# intput-selector.net
KiCad netlist of a schematic drawn in EAGLE
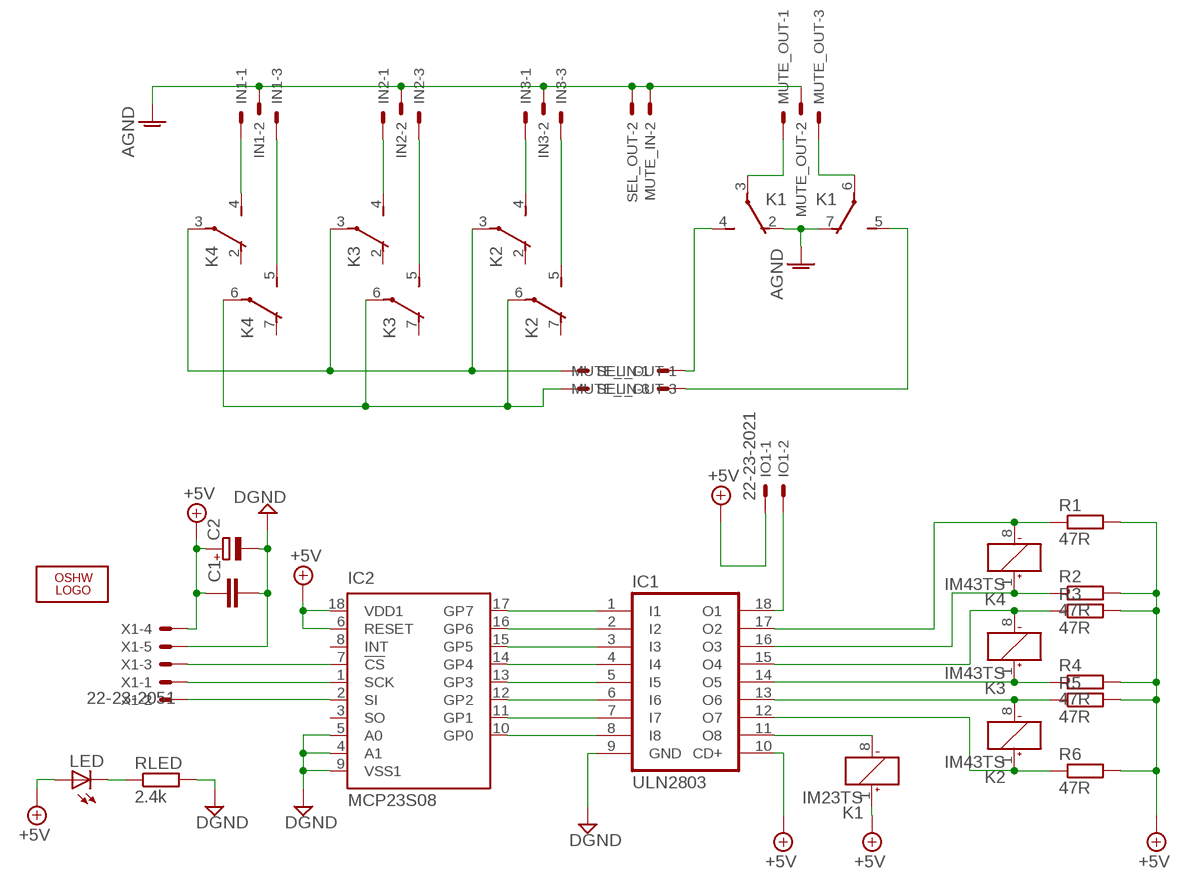
[diagram p0: schematic, sheet 1]

(export (version "E")
  (design (tool "Eeschema 10.0.6"))
  (components
    (comp (ref "C1")
      (value "C-EUC1206")
      (footprint "eagle-import:C1206")
      (libsource (lib "eagle-import") (part "C-EUC1206"))
    )
    (comp (ref "C2")
      (value "CPOL-EUC")
      (footprint "eagle-import:PANASONIC_C")
      (libsource (lib "eagle-import") (part "CPOL-EUC"))
    )
    (comp (ref "IC1")
      (value "ULN2803")
      (footprint "eagle-import:SO-18W")
      (libsource (lib "eagle-import") (part "ULN2803ADW"))
    )
    (comp (ref "IC2")
      (value "MCP23S08")
      (footprint "eagle-import:SO-18W")
      (libsource (lib "eagle-import") (part "MCP23S08-E/SO"))
    )
    (comp (ref "IN1")
      (value "22-23-2031")
      (footprint "eagle-import:22-23-2031")
      (fields (field (name "MF") "MOLEX"))
      (libsource (lib "eagle-import") (part "22-23-2031"))
    )
    (comp (ref "IN2")
      (value "22-23-2031")
      (footprint "eagle-import:22-23-2031")
      (fields (field (name "MF") "MOLEX"))
      (libsource (lib "eagle-import") (part "22-23-2031"))
    )
    (comp (ref "IN3")
      (value "22-23-2031")
      (footprint "eagle-import:22-23-2031")
      (fields (field (name "MF") "MOLEX"))
      (libsource (lib "eagle-import") (part "22-23-2031"))
    )
    (comp (ref "IO1")
      (value "22-23-2021")
      (footprint "eagle-import:22-23-2021")
      (fields (field (name "MF") "MOLEX"))
      (libsource (lib "eagle-import") (part "22-23-2021"))
    )
    (comp (ref "K1")
      (value "IM23TS")
      (footprint "eagle-import:IM43TS")
      (libsource (lib "eagle-import") (part "IM23TS"))
    )
    (comp (ref "K2")
      (value "IM43TS")
      (footprint "eagle-import:IM43TS")
      (libsource (lib "eagle-import") (part "IM43TS"))
    )
    (comp (ref "K3")
      (value "IM43TS")
      (footprint "eagle-import:IM43TS")
      (libsource (lib "eagle-import") (part "IM43TS"))
    )
    (comp (ref "K4")
      (value "IM43TS")
      (footprint "eagle-import:IM43TS")
      (libsource (lib "eagle-import") (part "IM43TS"))
    )
    (comp (ref "LED")
      (value "LEDCHIPLED_1206")
      (footprint "eagle-import:CHIPLED_1206")
      (libsource (lib "eagle-import") (part "LEDCHIPLED_1206"))
    )
    (comp (ref "LOGO1")
      (value "OSHW_LOGO_FILLX0200-NT")
      (footprint "eagle-import:OSHW_FILLX200_NOTEXT")
      (libsource (lib "eagle-import") (part "OSHW_LOGO_FILLX0200-NT"))
    )
    (comp (ref "MUTE_IN")
      (value "22-23-2031")
      (footprint "eagle-import:22-23-2031")
      (fields (field (name "MF") "MOLEX"))
      (libsource (lib "eagle-import") (part "22-23-2031"))
    )
    (comp (ref "MUTE_OUT")
      (value "22-23-2031")
      (footprint "eagle-import:22-23-2031")
      (fields (field (name "MF") "MOLEX"))
      (libsource (lib "eagle-import") (part "22-23-2031"))
    )
    (comp (ref "R1")
      (value "47R")
      (footprint "eagle-import:R1206")
      (libsource (lib "eagle-import") (part "R-EU_R1206"))
    )
    (comp (ref "R2")
      (value "47R")
      (footprint "eagle-import:R1206")
      (libsource (lib "eagle-import") (part "R-EU_R1206"))
    )
    (comp (ref "R3")
      (value "47R")
      (footprint "eagle-import:R1206")
      (libsource (lib "eagle-import") (part "R-EU_R1206"))
    )
    (comp (ref "R4")
      (value "47R")
      (footprint "eagle-import:R1206")
      (libsource (lib "eagle-import") (part "R-EU_R1206"))
    )
    (comp (ref "R5")
      (value "47R")
      (footprint "eagle-import:R1206")
      (libsource (lib "eagle-import") (part "R-EU_R1206"))
    )
    (comp (ref "R6")
      (value "47R")
      (footprint "eagle-import:R1206")
      (libsource (lib "eagle-import") (part "R-EU_R1206"))
    )
    (comp (ref "RLED")
      (value "2.4k")
      (footprint "eagle-import:R1206")
      (libsource (lib "eagle-import") (part "R-EU_R1206"))
    )
    (comp (ref "SEL_OUT")
      (value "22-23-2031")
      (footprint "eagle-import:22-23-2031")
      (fields (field (name "MF") "MOLEX"))
      (libsource (lib "eagle-import") (part "22-23-2031"))
    )
    (comp (ref "X1")
      (value "22-23-2051")
      (footprint "eagle-import:22-23-2051")
      (fields (field (name "MF") "MOLEX"))
      (libsource (lib "eagle-import") (part "22-23-2051"))
    )
  )
  (nets
    (net (code "1") (name "+5V") (class "Default")
      (node (ref "C1") (pin "1") (pinfunction "1_1") (pintype "passive"))
      (node (ref "C2") (pin "+") (pinfunction "+_+") (pintype "passive"))
      (node (ref "IC1") (pin "10") (pinfunction "CD+_10") (pintype "passive"))
      (node (ref "IC2") (pin "18") (pinfunction "VDD1_18") (pintype "power_in"))
      (node (ref "IC2") (pin "6") (pinfunction "RESET_6") (pintype "input"))
      (node (ref "IO1") (pin "1") (pinfunction "S_1") (pintype "passive"))
      (node (ref "K1") (pin "1") (pinfunction "+_1") (pintype "passive"))
      (node (ref "LED") (pin "A") (pinfunction "A_A") (pintype "passive"))
      (node (ref "R1") (pin "2") (pinfunction "2_2") (pintype "passive"))
      (node (ref "R2") (pin "2") (pinfunction "2_2") (pintype "passive"))
      (node (ref "R3") (pin "2") (pinfunction "2_2") (pintype "passive"))
      (node (ref "R4") (pin "2") (pinfunction "2_2") (pintype "passive"))
      (node (ref "R5") (pin "2") (pinfunction "2_2") (pintype "passive"))
      (node (ref "R6") (pin "2") (pinfunction "2_2") (pintype "passive"))
      (node (ref "X1") (pin "4") (pinfunction "S_4") (pintype "passive"))
    )
    (net (code "2") (name "AGND") (class "Default")
      (node (ref "IN1") (pin "2") (pinfunction "S_2") (pintype "passive"))
      (node (ref "IN2") (pin "2") (pinfunction "S_2") (pintype "passive"))
      (node (ref "IN3") (pin "2") (pinfunction "S_2") (pintype "passive"))
      (node (ref "K1") (pin "2") (pinfunction "O_2") (pintype "passive"))
      (node (ref "K1") (pin "7") (pinfunction "O_7") (pintype "passive"))
      (node (ref "MUTE_IN") (pin "2") (pinfunction "S_2") (pintype "passive"))
      (node (ref "MUTE_OUT") (pin "2") (pinfunction "S_2") (pintype "passive"))
      (node (ref "SEL_OUT") (pin "2") (pinfunction "S_2") (pintype "passive"))
    )
    (net (code "3") (name "DGND") (class "Default")
      (node (ref "C1") (pin "2") (pinfunction "2_2") (pintype "passive"))
      (node (ref "C2") (pin "-") (pinfunction "-_-") (pintype "passive"))
      (node (ref "IC1") (pin "9") (pinfunction "GND_9") (pintype "power_in"))
      (node (ref "IC2") (pin "4") (pinfunction "A1_4") (pintype "input"))
      (node (ref "IC2") (pin "5") (pinfunction "A0_5") (pintype "input"))
      (node (ref "IC2") (pin "9") (pinfunction "VSS1_9") (pintype "power_in"))
      (node (ref "RLED") (pin "2") (pinfunction "2_2") (pintype "passive"))
      (node (ref "X1") (pin "5") (pinfunction "S_5") (pintype "passive"))
    )
    (net (code "4") (name "Net-(IC1-I1)") (class "Default")
      (node (ref "IC1") (pin "1") (pinfunction "I1_1") (pintype "input"))
      (node (ref "IC2") (pin "17") (pinfunction "GP7_17") (pintype "bidirectional"))
    )
    (net (code "5") (name "Net-(IC1-I2)") (class "Default")
      (node (ref "IC1") (pin "2") (pinfunction "I2_2") (pintype "input"))
      (node (ref "IC2") (pin "16") (pinfunction "GP6_16") (pintype "bidirectional"))
    )
    (net (code "6") (name "Net-(IC1-I3)") (class "Default")
      (node (ref "IC1") (pin "3") (pinfunction "I3_3") (pintype "input"))
      (node (ref "IC2") (pin "15") (pinfunction "GP5_15") (pintype "bidirectional"))
    )
    (net (code "7") (name "Net-(IC1-I4)") (class "Default")
      (node (ref "IC1") (pin "4") (pinfunction "I4_4") (pintype "input"))
      (node (ref "IC2") (pin "14") (pinfunction "GP4_14") (pintype "bidirectional"))
    )
    (net (code "8") (name "Net-(IC1-I5)") (class "Default")
      (node (ref "IC1") (pin "5") (pinfunction "I5_5") (pintype "input"))
      (node (ref "IC2") (pin "13") (pinfunction "GP3_13") (pintype "bidirectional"))
    )
    (net (code "9") (name "Net-(IC1-I6)") (class "Default")
      (node (ref "IC1") (pin "6") (pinfunction "I6_6") (pintype "input"))
      (node (ref "IC2") (pin "12") (pinfunction "GP2_12") (pintype "bidirectional"))
    )
    (net (code "10") (name "Net-(IC1-I7)") (class "Default")
      (node (ref "IC1") (pin "7") (pinfunction "I7_7") (pintype "input"))
      (node (ref "IC2") (pin "11") (pinfunction "GP1_11") (pintype "bidirectional"))
    )
    (net (code "11") (name "Net-(IC1-I8)") (class "Default")
      (node (ref "IC1") (pin "8") (pinfunction "I8_8") (pintype "input"))
      (node (ref "IC2") (pin "10") (pinfunction "GP0_10") (pintype "bidirectional"))
    )
    (net (code "12") (name "Net-(IC1-O1)") (class "Default")
      (node (ref "IC1") (pin "18") (pinfunction "O1_18") (pintype "open_collector"))
      (node (ref "IO1") (pin "2") (pinfunction "S_2") (pintype "passive"))
    )
    (net (code "13") (name "Net-(IC1-O2)") (class "Default")
      (node (ref "IC1") (pin "17") (pinfunction "O2_17") (pintype "open_collector"))
      (node (ref "K4") (pin "8") (pinfunction "-_8") (pintype "passive"))
      (node (ref "R1") (pin "1") (pinfunction "1_1") (pintype "passive"))
    )
    (net (code "14") (name "Net-(IC1-O3)") (class "Default")
      (node (ref "IC1") (pin "16") (pinfunction "O3_16") (pintype "open_collector"))
      (node (ref "K4") (pin "1") (pinfunction "+_1") (pintype "passive"))
      (node (ref "R2") (pin "1") (pinfunction "1_1") (pintype "passive"))
    )
    (net (code "15") (name "Net-(IC1-O4)") (class "Default")
      (node (ref "IC1") (pin "15") (pinfunction "O4_15") (pintype "open_collector"))
      (node (ref "K3") (pin "8") (pinfunction "-_8") (pintype "passive"))
      (node (ref "R3") (pin "1") (pinfunction "1_1") (pintype "passive"))
    )
    (net (code "16") (name "Net-(IC1-O5)") (class "Default")
      (node (ref "IC1") (pin "14") (pinfunction "O5_14") (pintype "open_collector"))
      (node (ref "K3") (pin "1") (pinfunction "+_1") (pintype "passive"))
      (node (ref "R4") (pin "1") (pinfunction "1_1") (pintype "passive"))
    )
    (net (code "17") (name "Net-(IC1-O6)") (class "Default")
      (node (ref "IC1") (pin "13") (pinfunction "O6_13") (pintype "open_collector"))
      (node (ref "K2") (pin "8") (pinfunction "-_8") (pintype "passive"))
      (node (ref "R5") (pin "1") (pinfunction "1_1") (pintype "passive"))
    )
    (net (code "18") (name "Net-(IC1-O7)") (class "Default")
      (node (ref "IC1") (pin "12") (pinfunction "O7_12") (pintype "open_collector"))
      (node (ref "K2") (pin "1") (pinfunction "+_1") (pintype "passive"))
      (node (ref "R6") (pin "1") (pinfunction "1_1") (pintype "passive"))
    )
    (net (code "19") (name "Net-(IC1-O8)") (class "Default")
      (node (ref "IC1") (pin "11") (pinfunction "O8_11") (pintype "open_collector"))
      (node (ref "K1") (pin "8") (pinfunction "-_8") (pintype "passive"))
    )
    (net (code "20") (name "Net-(IC2-SCK)") (class "Default")
      (node (ref "IC2") (pin "1") (pinfunction "SCK_1") (pintype "input"))
      (node (ref "X1") (pin "1") (pinfunction "S_1") (pintype "passive"))
    )
    (net (code "21") (name "Net-(IC2-SI)") (class "Default")
      (node (ref "IC2") (pin "2") (pinfunction "SI_2") (pintype "input"))
      (node (ref "X1") (pin "2") (pinfunction "S_2") (pintype "passive"))
    )
    (net (code "22") (name "Net-(IC2-~{CS})") (class "Default")
      (node (ref "IC2") (pin "7") (pinfunction "~{CS}_7") (pintype "input"))
      (node (ref "X1") (pin "3") (pinfunction "S_3") (pintype "passive"))
    )
    (net (code "23") (name "Net-(IN1A-S)") (class "Default")
      (node (ref "IN1") (pin "1") (pinfunction "S_1") (pintype "passive"))
      (node (ref "K4") (pin "4") (pinfunction "S_4") (pintype "passive"))
    )
    (net (code "24") (name "Net-(IN1C-S)") (class "Default")
      (node (ref "IN1") (pin "3") (pinfunction "S_3") (pintype "passive"))
      (node (ref "K4") (pin "5") (pinfunction "S_5") (pintype "passive"))
    )
    (net (code "25") (name "Net-(IN2A-S)") (class "Default")
      (node (ref "IN2") (pin "1") (pinfunction "S_1") (pintype "passive"))
      (node (ref "K3") (pin "4") (pinfunction "S_4") (pintype "passive"))
    )
    (net (code "26") (name "Net-(IN2C-S)") (class "Default")
      (node (ref "IN2") (pin "3") (pinfunction "S_3") (pintype "passive"))
      (node (ref "K3") (pin "5") (pinfunction "S_5") (pintype "passive"))
    )
    (net (code "27") (name "Net-(IN3A-S)") (class "Default")
      (node (ref "IN3") (pin "1") (pinfunction "S_1") (pintype "passive"))
      (node (ref "K2") (pin "4") (pinfunction "S_4") (pintype "passive"))
    )
    (net (code "28") (name "Net-(IN3C-S)") (class "Default")
      (node (ref "IN3") (pin "3") (pinfunction "S_3") (pintype "passive"))
      (node (ref "K2") (pin "5") (pinfunction "S_5") (pintype "passive"))
    )
    (net (code "29") (name "Net-(K1B-P)") (class "Default")
      (node (ref "K1") (pin "3") (pinfunction "P_3") (pintype "passive"))
      (node (ref "MUTE_OUT") (pin "1") (pinfunction "S_1") (pintype "passive"))
    )
    (net (code "30") (name "Net-(K1B-S)") (class "Default")
      (node (ref "K1") (pin "4") (pinfunction "S_4") (pintype "passive"))
      (node (ref "MUTE_IN") (pin "1") (pinfunction "S_1") (pintype "passive"))
    )
    (net (code "31") (name "Net-(K1C-P)") (class "Default")
      (node (ref "K1") (pin "6") (pinfunction "P_6") (pintype "passive"))
      (node (ref "MUTE_OUT") (pin "3") (pinfunction "S_3") (pintype "passive"))
    )
    (net (code "32") (name "Net-(K1C-S)") (class "Default")
      (node (ref "K1") (pin "5") (pinfunction "S_5") (pintype "passive"))
      (node (ref "MUTE_IN") (pin "3") (pinfunction "S_3") (pintype "passive"))
    )
    (net (code "33") (name "Net-(K2B-P)") (class "Default")
      (node (ref "K2") (pin "3") (pinfunction "P_3") (pintype "passive"))
      (node (ref "K3") (pin "3") (pinfunction "P_3") (pintype "passive"))
      (node (ref "K4") (pin "3") (pinfunction "P_3") (pintype "passive"))
      (node (ref "SEL_OUT") (pin "1") (pinfunction "S_1") (pintype "passive"))
    )
    (net (code "34") (name "Net-(K2C-P)") (class "Default")
      (node (ref "K2") (pin "6") (pinfunction "P_6") (pintype "passive"))
      (node (ref "K3") (pin "6") (pinfunction "P_6") (pintype "passive"))
      (node (ref "K4") (pin "6") (pinfunction "P_6") (pintype "passive"))
      (node (ref "SEL_OUT") (pin "3") (pinfunction "S_3") (pintype "passive"))
    )
    (net (code "35") (name "Net-(LED-PadC)") (class "Default")
      (node (ref "LED") (pin "C") (pinfunction "C_C") (pintype "passive"))
      (node (ref "RLED") (pin "1") (pinfunction "1_1") (pintype "passive"))
    )
    (net (code "36") (name "unconnected-(IC2-INT-Pad8)") (class "Default")
      (node (ref "IC2") (pin "8") (pinfunction "INT_8") (pintype "output"))
    )
    (net (code "37") (name "unconnected-(IC2-SO-Pad3)") (class "Default")
      (node (ref "IC2") (pin "3") (pinfunction "SO_3") (pintype "output"))
    )
    (net (code "38") (name "unconnected-(K2B-O-Pad2)") (class "Default")
      (node (ref "K2") (pin "2") (pinfunction "O_2") (pintype "passive"))
    )
    (net (code "39") (name "unconnected-(K2C-O-Pad7)") (class "Default")
      (node (ref "K2") (pin "7") (pinfunction "O_7") (pintype "passive"))
    )
    (net (code "40") (name "unconnected-(K3B-O-Pad2)") (class "Default")
      (node (ref "K3") (pin "2") (pinfunction "O_2") (pintype "passive"))
    )
    (net (code "41") (name "unconnected-(K3C-O-Pad7)") (class "Default")
      (node (ref "K3") (pin "7") (pinfunction "O_7") (pintype "passive"))
    )
    (net (code "42") (name "unconnected-(K4B-O-Pad2)") (class "Default")
      (node (ref "K4") (pin "2") (pinfunction "O_2") (pintype "passive"))
    )
    (net (code "43") (name "unconnected-(K4C-O-Pad7)") (class "Default")
      (node (ref "K4") (pin "7") (pinfunction "O_7") (pintype "passive"))
    )
  )
)
